# Power_supply.net
KiCad netlist of a schematic drawn in EAGLE
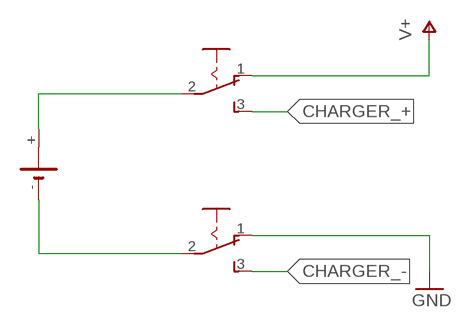
[diagram p0: schematic, sheet 1]

(export (version "E")
  (design (tool "Eeschema 10.0.6"))
  (components
    (comp (ref "G1")
      (value "CR1/2")
      (footprint "eagle-import:CR1_2")
      (libsource (lib "eagle-import") (part "CR1/2"))
    )
    (comp (ref "S1")
      (value "255SB")
      (footprint "eagle-import:255SB")
      (libsource (lib "eagle-import") (part "255SB"))
    )
    (comp (ref "S2")
      (value "255SB")
      (footprint "eagle-import:255SB")
      (libsource (lib "eagle-import") (part "255SB"))
    )
  )
  (nets
    (net (code "1") (name "CHARGER_+") (class "Default")
      (node (ref "S1") (pin "3") (pinfunction "S_3") (pintype "passive"))
    )
    (net (code "2") (name "CHARGER_-") (class "Default")
      (node (ref "S2") (pin "3") (pinfunction "S_3") (pintype "passive"))
    )
    (net (code "3") (name "GND") (class "Default")
      (node (ref "S2") (pin "1") (pinfunction "O_1") (pintype "passive"))
    )
    (net (code "4") (name "Net-(S1-P)") (class "Default")
      (node (ref "G1") (pin "+") (pinfunction "+_+") (pintype "passive"))
      (node (ref "S1") (pin "2") (pinfunction "P_2") (pintype "passive"))
    )
    (net (code "5") (name "Net-(S2-P)") (class "Default")
      (node (ref "G1") (pin "-") (pinfunction "-_-") (pintype "passive"))
      (node (ref "S2") (pin "2") (pinfunction "P_2") (pintype "passive"))
    )
    (net (code "6") (name "V+") (class "Default")
      (node (ref "S1") (pin "1") (pinfunction "O_1") (pintype "passive"))
    )
    (net (code "7") (name "unconnected-(G1-+-Pad+@1)") (class "Default")
      (node (ref "G1") (pin "+@1") (pinfunction "+_+@1") (pintype "passive"))
    )
  )
)
